# M18_36_Potis.net
KiCad netlist of a schematic drawn in EAGLE
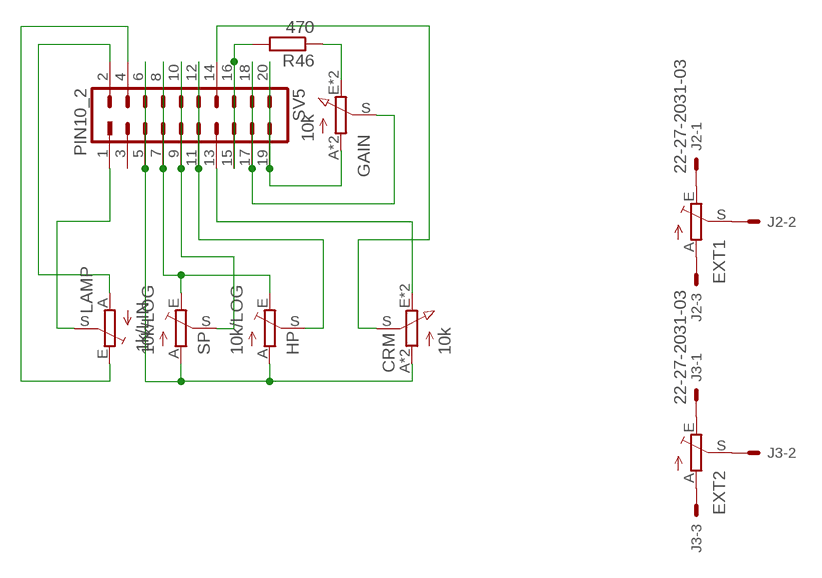
[diagram p0: schematic, sheet 1]

(export (version "E")
  (design (tool "Eeschema 10.0.6"))
  (components
    (comp (ref "CRM")
      (value "10k")
      (footprint "eagle-import:P_PT-10+15_KIEMELT")
      (libsource (lib "eagle-import") (part "P_EUPT10+15_K"))
    )
    (comp (ref "EXT1")
      (value "TRIM_EU-PT10")
      (footprint "eagle-import:PT-10")
      (libsource (lib "eagle-import") (part "TRIM_EU-PT10"))
    )
    (comp (ref "EXT2")
      (value "TRIM_EU-PT10")
      (footprint "eagle-import:PT-10")
      (libsource (lib "eagle-import") (part "TRIM_EU-PT10"))
    )
    (comp (ref "GAIN")
      (value "10k")
      (footprint "eagle-import:P_PT-10+15_KIEMELT")
      (libsource (lib "eagle-import") (part "P_EUPT10+15_K"))
    )
    (comp (ref "HP")
      (value "10k/LOG")
      (footprint "eagle-import:POT_NAR")
      (libsource (lib "eagle-import") (part "TRIM_EU-POT_WHOLE"))
    )
    (comp (ref "J2")
      (value "22-27-2031-03")
      (footprint "eagle-import:6410-03")
      (libsource (lib "eagle-import") (part "22-?-0327-2031"))
    )
    (comp (ref "J3")
      (value "22-27-2031-03")
      (footprint "eagle-import:6410-03")
      (libsource (lib "eagle-import") (part "22-?-0327-2031"))
    )
    (comp (ref "LAMP")
      (value "1k/LIN")
      (footprint "eagle-import:POT_NAR")
      (libsource (lib "eagle-import") (part "TRIM_EU-POT_WHOLE"))
    )
    (comp (ref "R46")
      (value "470")
      (footprint "eagle-import:R0805")
      (libsource (lib "eagle-import") (part "R-EU_R0805"))
    )
    (comp (ref "SP")
      (value "10k/LOG")
      (footprint "eagle-import:POT_NAR")
      (libsource (lib "eagle-import") (part "TRIM_EU-POT_WHOLE"))
    )
    (comp (ref "SV5")
      (value "PIN10_2")
      (footprint "eagle-import:PIN10_2")
      (libsource (lib "eagle-import") (part "PIN10_2"))
    )
  )
  (nets
    (net (code "1") (name "Net-(CRM-A-PadA1)") (class "Default")
      (node (ref "CRM") (pin "A") (pinfunction "A_A") (pintype "passive"))
      (node (ref "CRM") (pin "A1") (pinfunction "A_A1") (pintype "passive"))
      (node (ref "HP") (pin "A") (pinfunction "A_A") (pintype "passive"))
      (node (ref "SP") (pin "A") (pinfunction "A_A") (pintype "passive"))
      (node (ref "SV5") (pin "5") (pinfunction "5_5") (pintype "passive"))
      (node (ref "SV5") (pin "6") (pinfunction "6_6") (pintype "passive"))
    )
    (net (code "2") (name "Net-(CRM-E-PadE1)") (class "Default")
      (node (ref "CRM") (pin "E") (pinfunction "E_E") (pintype "passive"))
      (node (ref "CRM") (pin "E1") (pinfunction "E_E1") (pintype "passive"))
      (node (ref "SV5") (pin "13") (pinfunction "13_13") (pintype "passive"))
    )
    (net (code "3") (name "Net-(CRM-PadS)") (class "Default")
      (node (ref "CRM") (pin "S") (pinfunction "S_S") (pintype "passive"))
      (node (ref "SV5") (pin "14") (pinfunction "14_14") (pintype "passive"))
    )
    (net (code "4") (name "Net-(GAIN-A-PadA1)") (class "Default")
      (node (ref "GAIN") (pin "A") (pinfunction "A_A") (pintype "passive"))
      (node (ref "GAIN") (pin "A1") (pinfunction "A_A1") (pintype "passive"))
      (node (ref "SV5") (pin "19") (pinfunction "19_19") (pintype "passive"))
      (node (ref "SV5") (pin "20") (pinfunction "20_20") (pintype "passive"))
    )
    (net (code "5") (name "Net-(GAIN-E-PadE1)") (class "Default")
      (node (ref "GAIN") (pin "E") (pinfunction "E_E") (pintype "passive"))
      (node (ref "GAIN") (pin "E1") (pinfunction "E_E1") (pintype "passive"))
      (node (ref "R46") (pin "1") (pinfunction "1_1") (pintype "passive"))
    )
    (net (code "6") (name "Net-(GAIN-PadS)") (class "Default")
      (node (ref "GAIN") (pin "S") (pinfunction "S_S") (pintype "passive"))
      (node (ref "SV5") (pin "17") (pinfunction "17_17") (pintype "passive"))
      (node (ref "SV5") (pin "18") (pinfunction "18_18") (pintype "passive"))
    )
    (net (code "7") (name "Net-(HP-PadE)") (class "Default")
      (node (ref "HP") (pin "E") (pinfunction "E_E") (pintype "passive"))
      (node (ref "SP") (pin "E") (pinfunction "E_E") (pintype "passive"))
      (node (ref "SV5") (pin "7") (pinfunction "7_7") (pintype "passive"))
      (node (ref "SV5") (pin "8") (pinfunction "8_8") (pintype "passive"))
    )
    (net (code "8") (name "Net-(HP-PadS)") (class "Default")
      (node (ref "HP") (pin "S") (pinfunction "S_S") (pintype "passive"))
      (node (ref "SV5") (pin "11") (pinfunction "11_11") (pintype "passive"))
      (node (ref "SV5") (pin "12") (pinfunction "12_12") (pintype "passive"))
    )
    (net (code "9") (name "Net-(J2A-S)") (class "Default")
      (node (ref "EXT1") (pin "E") (pinfunction "E_E") (pintype "passive"))
      (node (ref "J2") (pin "1") (pinfunction "S_1") (pintype "passive"))
    )
    (net (code "10") (name "Net-(J2B-S)") (class "Default")
      (node (ref "EXT1") (pin "S") (pinfunction "S_S") (pintype "passive"))
      (node (ref "J2") (pin "2") (pinfunction "S_2") (pintype "passive"))
    )
    (net (code "11") (name "Net-(J2C-S)") (class "Default")
      (node (ref "EXT1") (pin "A") (pinfunction "A_A") (pintype "passive"))
      (node (ref "J2") (pin "3") (pinfunction "S_3") (pintype "passive"))
    )
    (net (code "12") (name "Net-(J3A-S)") (class "Default")
      (node (ref "EXT2") (pin "E") (pinfunction "E_E") (pintype "passive"))
      (node (ref "J3") (pin "1") (pinfunction "S_1") (pintype "passive"))
    )
    (net (code "13") (name "Net-(J3B-S)") (class "Default")
      (node (ref "EXT2") (pin "S") (pinfunction "S_S") (pintype "passive"))
      (node (ref "J3") (pin "2") (pinfunction "S_2") (pintype "passive"))
    )
    (net (code "14") (name "Net-(J3C-S)") (class "Default")
      (node (ref "EXT2") (pin "A") (pinfunction "A_A") (pintype "passive"))
      (node (ref "J3") (pin "3") (pinfunction "S_3") (pintype "passive"))
    )
    (net (code "15") (name "Net-(LAMP-PadA)") (class "Default")
      (node (ref "LAMP") (pin "A") (pinfunction "A_A") (pintype "passive"))
      (node (ref "SV5") (pin "2") (pinfunction "2_2") (pintype "passive"))
    )
    (net (code "16") (name "Net-(LAMP-PadE)") (class "Default")
      (node (ref "LAMP") (pin "E") (pinfunction "E_E") (pintype "passive"))
      (node (ref "SV5") (pin "4") (pinfunction "4_4") (pintype "passive"))
    )
    (net (code "17") (name "Net-(LAMP-PadS)") (class "Default")
      (node (ref "LAMP") (pin "S") (pinfunction "S_S") (pintype "passive"))
      (node (ref "SV5") (pin "1") (pinfunction "1_1") (pintype "passive"))
    )
    (net (code "18") (name "Net-(R46-Pad2)") (class "Default")
      (node (ref "R46") (pin "2") (pinfunction "2_2") (pintype "passive"))
      (node (ref "SV5") (pin "15") (pinfunction "15_15") (pintype "passive"))
      (node (ref "SV5") (pin "16") (pinfunction "16_16") (pintype "passive"))
    )
    (net (code "19") (name "Net-(SP-PadS)") (class "Default")
      (node (ref "SP") (pin "S") (pinfunction "S_S") (pintype "passive"))
      (node (ref "SV5") (pin "10") (pinfunction "10_10") (pintype "passive"))
      (node (ref "SV5") (pin "9") (pinfunction "9_9") (pintype "passive"))
    )
    (net (code "20") (name "unconnected-(SV5-Pad3)") (class "Default")
      (node (ref "SV5") (pin "3") (pinfunction "3_3") (pintype "passive"))
    )
  )
)
